# ahrs.net
KiCad netlist of a schematic drawn in EAGLE
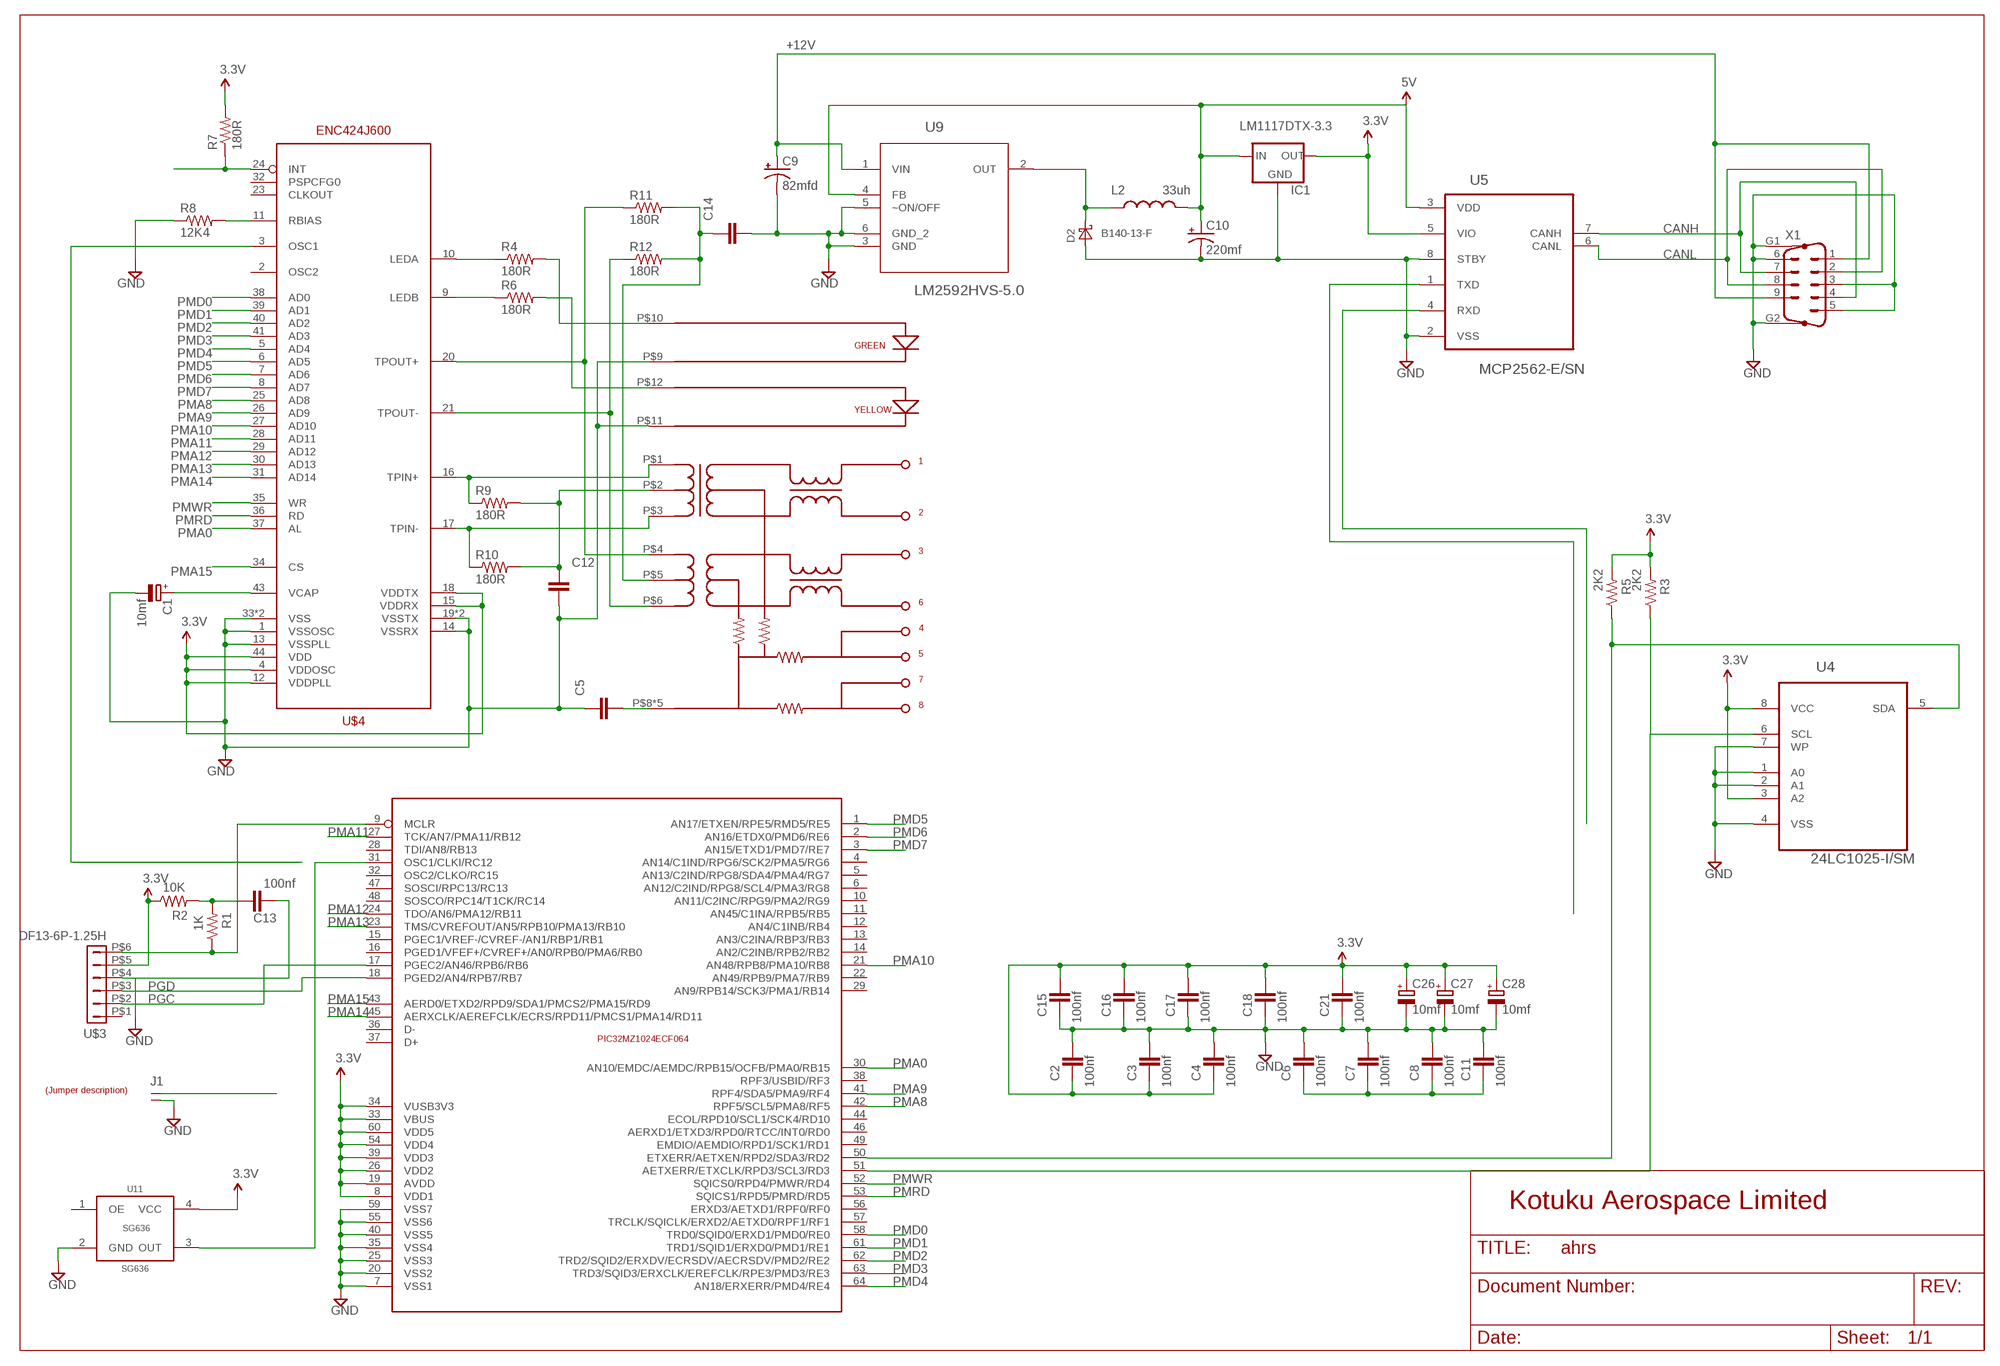
[diagram p0: schematic, sheet 1]

(export (version "E")
  (design (tool "Eeschema 10.0.6"))
  (components
    (comp (ref "C1")
      (value "10mf")
      (footprint "eagle-import:SMC_A")
      (libsource (lib "eagle-import") (part "CAPACITOR_POL-SMC_A"))
    )
    (comp (ref "C2")
      (value "100nf")
      (footprint "eagle-import:C805")
      (libsource (lib "eagle-import") (part "CAPACITOR_NPOL-0805"))
    )
    (comp (ref "C3")
      (value "100nf")
      (footprint "eagle-import:C805")
      (libsource (lib "eagle-import") (part "CAPACITOR_NPOL-0805"))
    )
    (comp (ref "C4")
      (value "100nf")
      (footprint "eagle-import:C805")
      (libsource (lib "eagle-import") (part "CAPACITOR_NPOL-0805"))
    )
    (comp (ref "C5")
      (value "CAPACITOR_NPOL-1206")
      (footprint "eagle-import:C1206")
      (libsource (lib "eagle-import") (part "kotuku_CAPACITOR_NPOL-1206"))
    )
    (comp (ref "C6")
      (value "100nf")
      (footprint "eagle-import:C805")
      (libsource (lib "eagle-import") (part "CAPACITOR_NPOL-0805"))
    )
    (comp (ref "C7")
      (value "100nf")
      (footprint "eagle-import:C805")
      (libsource (lib "eagle-import") (part "CAPACITOR_NPOL-0805"))
    )
    (comp (ref "C8")
      (value "100nf")
      (footprint "eagle-import:C805")
      (libsource (lib "eagle-import") (part "CAPACITOR_NPOL-0805"))
    )
    (comp (ref "C9")
      (value "82mfd")
      (footprint "eagle-import:SVPF-E7")
      (libsource (lib "eagle-import") (part "CAPACITOR_POL-SVPF-E7"))
    )
    (comp (ref "C10")
      (value "220mf")
      (footprint "eagle-import:EIA7343")
      (libsource (lib "eagle-import") (part "CAP_POL7343"))
    )
    (comp (ref "C11")
      (value "100nf")
      (footprint "eagle-import:C805")
      (libsource (lib "eagle-import") (part "CAPACITOR_NPOL-0805"))
    )
    (comp (ref "C12")
      (value "CAPACITOR_NPOL-0603")
      (footprint "eagle-import:C603")
      (libsource (lib "eagle-import") (part "kotuku_CAPACITOR_NPOL-0603"))
    )
    (comp (ref "C13")
      (value "100nf")
      (footprint "eagle-import:C805")
      (libsource (lib "eagle-import") (part "CAPACITOR_NPOL-0805"))
    )
    (comp (ref "C14")
      (value "CAPACITOR_NPOL-0603")
      (footprint "eagle-import:C603")
      (libsource (lib "eagle-import") (part "kotuku_CAPACITOR_NPOL-0603"))
    )
    (comp (ref "C15")
      (value "100nf")
      (footprint "eagle-import:C805")
      (libsource (lib "eagle-import") (part "CAPACITOR_NPOL-0805"))
    )
    (comp (ref "C16")
      (value "100nf")
      (footprint "eagle-import:C805")
      (libsource (lib "eagle-import") (part "CAPACITOR_NPOL-0805"))
    )
    (comp (ref "C17")
      (value "100nf")
      (footprint "eagle-import:C805")
      (libsource (lib "eagle-import") (part "CAPACITOR_NPOL-0805"))
    )
    (comp (ref "C18")
      (value "100nf")
      (footprint "eagle-import:C805")
      (libsource (lib "eagle-import") (part "CAPACITOR_NPOL-0805"))
    )
    (comp (ref "C21")
      (value "100nf")
      (footprint "eagle-import:C805")
      (libsource (lib "eagle-import") (part "CAPACITOR_NPOL-0805"))
    )
    (comp (ref "C26")
      (value "10mf")
      (footprint "eagle-import:SMC_A")
      (libsource (lib "eagle-import") (part "CAPACITOR_POL-SMC_A"))
    )
    (comp (ref "C27")
      (value "10mf")
      (footprint "eagle-import:SMC_A")
      (libsource (lib "eagle-import") (part "CAPACITOR_POL-SMC_A"))
    )
    (comp (ref "C28")
      (value "10mf")
      (footprint "eagle-import:SMC_A")
      (libsource (lib "eagle-import") (part "CAPACITOR_POL-SMC_A"))
    )
    (comp (ref "D2")
      (value "B140-13-F")
      (footprint "eagle-import:SMA")
      (libsource (lib "eagle-import") (part "DIODE-SCHOTTKY-SMA"))
    )
    (comp (ref "IC1")
      (value "LM1117DTX-3.3")
      (footprint "eagle-import:TO252")
      (libsource (lib "eagle-import") (part "LM1117DTX-3.3"))
    )
    (comp (ref "J1")
      (value "JUMPER-1X2")
      (footprint "eagle-import:JUMPER-1X2")
      (libsource (lib "eagle-import") (part "JUMPER-1X2"))
    )
    (comp (ref "L2")
      (value "33uh")
      (footprint "eagle-import:1812")
      (libsource (lib "eagle-import") (part "INDUCTOR"))
    )
    (comp (ref "R1")
      (value "1K")
      (footprint "eagle-import:0603-RES")
      (fields (field (name "PARTNO") "ERJ-3GEYJ103V"))
      (libsource (lib "eagle-import") (part "RESISTOR0603-RES"))
    )
    (comp (ref "R2")
      (value "10K")
      (footprint "eagle-import:0603-RES")
      (fields (field (name "PARTNO") "ERJ-3GEYJ103V"))
      (libsource (lib "eagle-import") (part "RESISTOR0603-RES"))
    )
    (comp (ref "R3")
      (value "2K2")
      (footprint "eagle-import:0603-RES")
      (fields (field (name "PARTNO") "ERJ-3GEYJ103V"))
      (libsource (lib "eagle-import") (part "RESISTOR0603-RES"))
    )
    (comp (ref "R4")
      (value "180R")
      (footprint "eagle-import:0603-RES")
      (libsource (lib "eagle-import") (part "kotuku_RESISTOR0603-RES"))
    )
    (comp (ref "R5")
      (value "2K2")
      (footprint "eagle-import:0603-RES")
      (fields (field (name "PARTNO") "ERJ-3GEYJ103V"))
      (libsource (lib "eagle-import") (part "RESISTOR0603-RES"))
    )
    (comp (ref "R6")
      (value "180R")
      (footprint "eagle-import:0603-RES")
      (libsource (lib "eagle-import") (part "kotuku_RESISTOR0603-RES"))
    )
    (comp (ref "R7")
      (value "180R")
      (footprint "eagle-import:0603-RES")
      (libsource (lib "eagle-import") (part "kotuku_RESISTOR0603-RES"))
    )
    (comp (ref "R8")
      (value "12K4")
      (footprint "eagle-import:0603-RES")
      (libsource (lib "eagle-import") (part "kotuku_RESISTOR0603-RES"))
    )
    (comp (ref "R9")
      (value "180R")
      (footprint "eagle-import:0603-RES")
      (libsource (lib "eagle-import") (part "kotuku_RESISTOR0603-RES"))
    )
    (comp (ref "R10")
      (value "180R")
      (footprint "eagle-import:0603-RES")
      (libsource (lib "eagle-import") (part "kotuku_RESISTOR0603-RES"))
    )
    (comp (ref "R11")
      (value "180R")
      (footprint "eagle-import:0603-RES")
      (libsource (lib "eagle-import") (part "kotuku_RESISTOR0603-RES"))
    )
    (comp (ref "R12")
      (value "180R")
      (footprint "eagle-import:0603-RES")
      (libsource (lib "eagle-import") (part "kotuku_RESISTOR0603-RES"))
    )
    (comp (ref "U$1")
      (value "LABEL_JUMPER_1X2")
      (footprint "eagle-import:JUMP2_DESC")
      (fields (field (name "OFF") "Normal") (field (name "ON") "Reset"))
      (libsource (lib "eagle-import") (part "LABEL_JUMPER_1X2"))
    )
    (comp (ref "U$2")
      (value "PIC32MZ1024")
      (footprint "eagle-import:TQFP-64")
      (libsource (lib "eagle-import") (part "PIC32MZ1024"))
    )
    (comp (ref "U$3")
      (value "DF13-6P-1.25H")
      (footprint "eagle-import:DF13A-6P-1.25H")
      (libsource (lib "eagle-import") (part "DF13-6P-1.25H"))
    )
    (comp (ref "U$4")
      (value "ENC424J600")
      (footprint "eagle-import:TQFP44")
      (libsource (lib "eagle-import") (part "ENC424J600"))
    )
    (comp (ref "U$5")
      (value "J1B1211CCD")
      (footprint "eagle-import:J1B1211CCD")
      (libsource (lib "eagle-import") (part "J1B1211CCD"))
    )
    (comp (ref "U4")
      (value "24LC1025-I/SM")
      (footprint "eagle-import:SOIC8-N_MC")
      (libsource (lib "eagle-import") (part "24LC1025-I/SM"))
    )
    (comp (ref "U5")
      (value "MCP2562-E/SN")
      (footprint "eagle-import:SOIC-8N")
      (libsource (lib "eagle-import") (part "MCP2562-E/SN"))
    )
    (comp (ref "U9")
      (value "LM2592HVS-5.0")
      (footprint "eagle-import:TO170P1435X457-5N")
      (libsource (lib "eagle-import") (part "LM2592HVS-5.0"))
    )
    (comp (ref "U11")
      (value "SG636")
      (footprint "eagle-import:SG636")
      (fields (field (name "PARTNO") "SG-636PCE 10.000MHZ"))
      (libsource (lib "eagle-import") (part "SG636"))
    )
    (comp (ref "X1")
      (value "M09HP")
      (footprint "eagle-import:M09HP")
      (libsource (lib "eagle-import") (part "M09HP"))
    )
  )
  (nets
    (net (code "1") (name "/+12V") (class "Default")
      (node (ref "C9") (pin "P$2") (pinfunction "+_P$2") (pintype "passive"))
      (node (ref "U9") (pin "1") (pinfunction "VIN_1") (pintype "power_in"))
      (node (ref "X1") (pin "1") (pinfunction "1_1") (pintype "passive"))
      (node (ref "X1") (pin "9") (pinfunction "9_9") (pintype "passive"))
    )
    (net (code "2") (name "/CANH") (class "Default")
      (node (ref "U5") (pin "7") (pinfunction "CANH_7") (pintype "bidirectional"))
      (node (ref "X1") (pin "4") (pinfunction "4_4") (pintype "passive"))
      (node (ref "X1") (pin "7") (pinfunction "7_7") (pintype "passive"))
    )
    (net (code "3") (name "/CANL") (class "Default")
      (node (ref "U5") (pin "6") (pinfunction "CANL_6") (pintype "bidirectional"))
      (node (ref "X1") (pin "2") (pinfunction "2_2") (pintype "passive"))
      (node (ref "X1") (pin "8") (pinfunction "8_8") (pintype "passive"))
    )
    (net (code "4") (name "/PGC") (class "Default")
      (node (ref "U$2") (pin "17") (pinfunction "PGEC2/AN46/RPB6/RB6_17") (pintype "bidirectional"))
      (node (ref "U$3") (pin "P$2") (pinfunction "2_P$2") (pintype "passive"))
    )
    (net (code "5") (name "/PGD") (class "Default")
      (node (ref "U$2") (pin "18") (pinfunction "PGED2/AN4/RPB7/RB7_18") (pintype "bidirectional"))
      (node (ref "U$3") (pin "P$3") (pinfunction "3_P$3") (pintype "passive"))
    )
    (net (code "6") (name "/PMA0") (class "Default")
      (node (ref "U$2") (pin "30") (pinfunction "AN10/EMDC/AEMDC/RPB15/OCFB/PMA0/RB15_30") (pintype "bidirectional"))
      (node (ref "U$4") (pin "37") (pinfunction "AL_37") (pintype "bidirectional"))
    )
    (net (code "7") (name "/PMA8") (class "Default")
      (node (ref "U$2") (pin "42") (pinfunction "RPF5/SCL5/PMA8/RF5_42") (pintype "bidirectional"))
      (node (ref "U$4") (pin "25") (pinfunction "AD8_25") (pintype "bidirectional"))
    )
    (net (code "8") (name "/PMA9") (class "Default")
      (node (ref "U$2") (pin "41") (pinfunction "RPF4/SDA5/PMA9/RF4_41") (pintype "bidirectional"))
      (node (ref "U$4") (pin "26") (pinfunction "AD9_26") (pintype "bidirectional"))
    )
    (net (code "9") (name "/PMA10") (class "Default")
      (node (ref "U$2") (pin "21") (pinfunction "AN48/RPB8/PMA10/RB8_21") (pintype "bidirectional"))
      (node (ref "U$4") (pin "27") (pinfunction "AD10_27") (pintype "bidirectional"))
    )
    (net (code "10") (name "/PMA11") (class "Default")
      (node (ref "U$2") (pin "27") (pinfunction "TCK/AN7/PMA11/RB12_27") (pintype "bidirectional"))
      (node (ref "U$4") (pin "28") (pinfunction "AD11_28") (pintype "bidirectional"))
    )
    (net (code "11") (name "/PMA12") (class "Default")
      (node (ref "U$2") (pin "24") (pinfunction "TDO/AN6/PMA12/RB11_24") (pintype "bidirectional"))
      (node (ref "U$4") (pin "29") (pinfunction "AD12_29") (pintype "bidirectional"))
    )
    (net (code "12") (name "/PMA13") (class "Default")
      (node (ref "U$2") (pin "23") (pinfunction "TMS/CVREFOUT/AN5/RPB10/PMA13/RB10_23") (pintype "bidirectional"))
      (node (ref "U$4") (pin "30") (pinfunction "AD13_30") (pintype "bidirectional"))
    )
    (net (code "13") (name "/PMA14") (class "Default")
      (node (ref "U$2") (pin "45") (pinfunction "AERXCLK/AEREFCLK/ECRS/RPD11/PMCS1/PMA14/RD11_45") (pintype "bidirectional"))
      (node (ref "U$4") (pin "31") (pinfunction "AD14_31") (pintype "bidirectional"))
    )
    (net (code "14") (name "/PMA15") (class "Default")
      (node (ref "U$2") (pin "43") (pinfunction "AERD0/ETXD2/RPD9/SDA1/PMCS2/PMA15/RD9_43") (pintype "bidirectional"))
      (node (ref "U$4") (pin "34") (pinfunction "CS_34") (pintype "bidirectional"))
    )
    (net (code "15") (name "/PMD0") (class "Default")
      (node (ref "U$2") (pin "58") (pinfunction "TRD0/SQID0/ERXD1/PMD0/RE0_58") (pintype "bidirectional"))
      (node (ref "U$4") (pin "38") (pinfunction "AD0_38") (pintype "bidirectional"))
    )
    (net (code "16") (name "/PMD1") (class "Default")
      (node (ref "U$2") (pin "61") (pinfunction "TRD1/SQID1/ERXD0/PMD1/RE1_61") (pintype "bidirectional"))
      (node (ref "U$4") (pin "39") (pinfunction "AD1_39") (pintype "bidirectional"))
    )
    (net (code "17") (name "/PMD2") (class "Default")
      (node (ref "U$2") (pin "62") (pinfunction "TRD2/SQID2/ERXDV/ECRSDV/AECRSDV/PMD2/RE2_62") (pintype "bidirectional"))
      (node (ref "U$4") (pin "40") (pinfunction "AD2_40") (pintype "bidirectional"))
    )
    (net (code "18") (name "/PMD3") (class "Default")
      (node (ref "U$2") (pin "63") (pinfunction "TRD3/SQID3/ERXCLK/EREFCLK/RPE3/PMD3/RE3_63") (pintype "bidirectional"))
      (node (ref "U$4") (pin "41") (pinfunction "AD3_41") (pintype "bidirectional"))
    )
    (net (code "19") (name "/PMD4") (class "Default")
      (node (ref "U$2") (pin "64") (pinfunction "AN18/ERXERR/PMD4/RE4_64") (pintype "bidirectional"))
      (node (ref "U$4") (pin "5") (pinfunction "AD4_5") (pintype "bidirectional"))
    )
    (net (code "20") (name "/PMD5") (class "Default")
      (node (ref "U$2") (pin "1") (pinfunction "AN17/ETXEN/RPE5/RMD5/RE5_1") (pintype "bidirectional"))
      (node (ref "U$4") (pin "6") (pinfunction "AD5_6") (pintype "bidirectional"))
    )
    (net (code "21") (name "/PMD6") (class "Default")
      (node (ref "U$2") (pin "2") (pinfunction "AN16/ETDX0/PMD6/RE6_2") (pintype "bidirectional"))
      (node (ref "U$4") (pin "7") (pinfunction "AD6_7") (pintype "bidirectional"))
    )
    (net (code "22") (name "/PMD7") (class "Default")
      (node (ref "U$2") (pin "3") (pinfunction "AN15/ETXD1/PMD7/RE7_3") (pintype "bidirectional"))
      (node (ref "U$4") (pin "8") (pinfunction "AD7_8") (pintype "bidirectional"))
    )
    (net (code "23") (name "/PMRD") (class "Default")
      (node (ref "U$2") (pin "53") (pinfunction "SQICS1/RPD5/PMRD/RD5_53") (pintype "bidirectional"))
      (node (ref "U$4") (pin "36") (pinfunction "RD_36") (pintype "bidirectional"))
    )
    (net (code "24") (name "/PMWR") (class "Default")
      (node (ref "U$2") (pin "52") (pinfunction "SQICS0/RPD4/PMWR/RD4_52") (pintype "bidirectional"))
      (node (ref "U$4") (pin "35") (pinfunction "WR_35") (pintype "bidirectional"))
    )
    (net (code "25") (name "3.3V") (class "Default")
      (node (ref "C15") (pin "1") (pinfunction "1_1") (pintype "passive"))
      (node (ref "C16") (pin "1") (pinfunction "1_1") (pintype "passive"))
      (node (ref "C17") (pin "1") (pinfunction "1_1") (pintype "passive"))
      (node (ref "C18") (pin "1") (pinfunction "1_1") (pintype "passive"))
      (node (ref "C2") (pin "2") (pinfunction "2_2") (pintype "passive"))
      (node (ref "C21") (pin "1") (pinfunction "1_1") (pintype "passive"))
      (node (ref "C26") (pin "+") (pinfunction "+_+") (pintype "passive"))
      (node (ref "C27") (pin "+") (pinfunction "+_+") (pintype "passive"))
      (node (ref "C28") (pin "+") (pinfunction "+_+") (pintype "passive"))
      (node (ref "C3") (pin "2") (pinfunction "2_2") (pintype "passive"))
      (node (ref "C4") (pin "2") (pinfunction "2_2") (pintype "passive"))
      (node (ref "IC1") (pin "TAB") (pinfunction "OUT_TAB") (pintype "passive"))
      (node (ref "R2") (pin "1") (pinfunction "1_1") (pintype "passive"))
      (node (ref "R3") (pin "2") (pinfunction "2_2") (pintype "passive"))
      (node (ref "R5") (pin "2") (pinfunction "2_2") (pintype "passive"))
      (node (ref "R7") (pin "2") (pinfunction "2_2") (pintype "passive"))
      (node (ref "U$2") (pin "19") (pinfunction "AVDD_19") (pintype "bidirectional"))
      (node (ref "U$2") (pin "26") (pinfunction "VDD2_26") (pintype "bidirectional"))
      (node (ref "U$2") (pin "33") (pinfunction "VBUS_33") (pintype "bidirectional"))
      (node (ref "U$2") (pin "34") (pinfunction "VUSB3V3_34") (pintype "bidirectional"))
      (node (ref "U$2") (pin "39") (pinfunction "VDD3_39") (pintype "bidirectional"))
      (node (ref "U$2") (pin "54") (pinfunction "VDD4_54") (pintype "bidirectional"))
      (node (ref "U$2") (pin "60") (pinfunction "VDD5_60") (pintype "bidirectional"))
      (node (ref "U$2") (pin "8") (pinfunction "VDD1_8") (pintype "bidirectional"))
      (node (ref "U$3") (pin "P$5") (pinfunction "5_P$5") (pintype "passive"))
      (node (ref "U$4") (pin "12") (pinfunction "VDDPLL_12") (pintype "bidirectional"))
      (node (ref "U$4") (pin "15") (pinfunction "VDDRX_15") (pintype "bidirectional"))
      (node (ref "U$4") (pin "18") (pinfunction "VDDTX_18") (pintype "bidirectional"))
      (node (ref "U$4") (pin "4") (pinfunction "VDDOSC_4") (pintype "bidirectional"))
      (node (ref "U$4") (pin "44") (pinfunction "VDD_44") (pintype "bidirectional"))
      (node (ref "U11") (pin "4") (pinfunction "VCC_4") (pintype "power_in"))
      (node (ref "U4") (pin "3") (pinfunction "A2_3") (pintype "input"))
      (node (ref "U4") (pin "8") (pinfunction "VCC_8") (pintype "power_in"))
      (node (ref "U5") (pin "5") (pinfunction "VIO_5") (pintype "power_in"))
    )
    (net (code "26") (name "5V") (class "Default")
      (node (ref "C10") (pin "A") (pinfunction "+_A") (pintype "passive"))
      (node (ref "IC1") (pin "2") (pinfunction "IN_2") (pintype "input"))
      (node (ref "L2") (pin "2") (pinfunction "2_2") (pintype "passive"))
      (node (ref "U5") (pin "3") (pinfunction "VDD_3") (pintype "power_in"))
      (node (ref "U9") (pin "4") (pinfunction "FB_4") (pintype "input"))
    )
    (net (code "27") (name "GND") (class "Default")
      (node (ref "C1") (pin "-") (pinfunction "-_-") (pintype "passive"))
      (node (ref "C10") (pin "C") (pinfunction "-_C") (pintype "passive"))
      (node (ref "C11") (pin "1") (pinfunction "1_1") (pintype "passive"))
      (node (ref "C12") (pin "2") (pinfunction "2_2") (pintype "passive"))
      (node (ref "C13") (pin "2") (pinfunction "2_2") (pintype "passive"))
      (node (ref "C14") (pin "2") (pinfunction "2_2") (pintype "passive"))
      (node (ref "C15") (pin "2") (pinfunction "2_2") (pintype "passive"))
      (node (ref "C16") (pin "2") (pinfunction "2_2") (pintype "passive"))
      (node (ref "C17") (pin "2") (pinfunction "2_2") (pintype "passive"))
      (node (ref "C18") (pin "2") (pinfunction "2_2") (pintype "passive"))
      (node (ref "C2") (pin "1") (pinfunction "1_1") (pintype "passive"))
      (node (ref "C21") (pin "2") (pinfunction "2_2") (pintype "passive"))
      (node (ref "C26") (pin "-") (pinfunction "-_-") (pintype "passive"))
      (node (ref "C27") (pin "-") (pinfunction "-_-") (pintype "passive"))
      (node (ref "C28") (pin "-") (pinfunction "-_-") (pintype "passive"))
      (node (ref "C3") (pin "1") (pinfunction "1_1") (pintype "passive"))
      (node (ref "C4") (pin "1") (pinfunction "1_1") (pintype "passive"))
      (node (ref "C5") (pin "1") (pinfunction "1_1") (pintype "passive"))
      (node (ref "C6") (pin "1") (pinfunction "1_1") (pintype "passive"))
      (node (ref "C7") (pin "1") (pinfunction "1_1") (pintype "passive"))
      (node (ref "C8") (pin "1") (pinfunction "1_1") (pintype "passive"))
      (node (ref "C9") (pin "P$1") (pinfunction "-_P$1") (pintype "passive"))
      (node (ref "D2") (pin "A") (pinfunction "A_A") (pintype "passive"))
      (node (ref "IC1") (pin "1") (pinfunction "GND_1") (pintype "input"))
      (node (ref "J1") (pin "2") (pinfunction "2_2") (pintype "bidirectional"))
      (node (ref "R8") (pin "1") (pinfunction "1_1") (pintype "passive"))
      (node (ref "U$2") (pin "20") (pinfunction "VSS2_20") (pintype "bidirectional"))
      (node (ref "U$2") (pin "25") (pinfunction "VSS3_25") (pintype "bidirectional"))
      (node (ref "U$2") (pin "35") (pinfunction "VSS4_35") (pintype "bidirectional"))
      (node (ref "U$2") (pin "40") (pinfunction "VSS5_40") (pintype "bidirectional"))
      (node (ref "U$2") (pin "55") (pinfunction "VSS6_55") (pintype "bidirectional"))
      (node (ref "U$2") (pin "59") (pinfunction "VSS7_59") (pintype "bidirectional"))
      (node (ref "U$2") (pin "7") (pinfunction "VSS1_7") (pintype "bidirectional"))
      (node (ref "U$3") (pin "P$4") (pinfunction "4_P$4") (pintype "passive"))
      (node (ref "U$4") (pin "1") (pinfunction "VSSOSC_1") (pintype "bidirectional"))
      (node (ref "U$4") (pin "13") (pinfunction "VSSPLL_13") (pintype "bidirectional"))
      (node (ref "U$4") (pin "14") (pinfunction "VSSRX_14") (pintype "bidirectional"))
      (node (ref "U$4") (pin "19") (pinfunction "VSSTX_19") (pintype "bidirectional"))
      (node (ref "U$4") (pin "22") (pinfunction "VSSTX_22") (pintype "bidirectional"))
      (node (ref "U$4") (pin "33") (pinfunction "VSS_33") (pintype "bidirectional"))
      (node (ref "U$4") (pin "42") (pinfunction "VSS_42") (pintype "bidirectional"))
      (node (ref "U$5") (pin "P$11") (pinfunction "YELLOW_K_P$11") (pintype "bidirectional"))
      (node (ref "U$5") (pin "P$9") (pinfunction "GREEN_K_P$9") (pintype "bidirectional"))
      (node (ref "U11") (pin "2") (pinfunction "GND_2") (pintype "power_in"))
      (node (ref "U4") (pin "1") (pinfunction "A0_1") (pintype "input"))
      (node (ref "U4") (pin "2") (pinfunction "A1_2") (pintype "input"))
      (node (ref "U4") (pin "4") (pinfunction "VSS_4") (pintype "passive"))
      (node (ref "U4") (pin "7") (pinfunction "WP_7") (pintype "input"))
      (node (ref "U5") (pin "2") (pinfunction "VSS_2") (pintype "power_in"))
      (node (ref "U5") (pin "8") (pinfunction "STBY_8") (pintype "input"))
      (node (ref "U9") (pin "3") (pinfunction "GND_3") (pintype "passive"))
      (node (ref "U9") (pin "5") (pinfunction "~{ON/OFF}_5") (pintype "input"))
      (node (ref "U9") (pin "6") (pinfunction "GND_2_6") (pintype "passive"))
      (node (ref "X1") (pin "3") (pinfunction "3_3") (pintype "passive"))
      (node (ref "X1") (pin "5") (pinfunction "5_5") (pintype "passive"))
      (node (ref "X1") (pin "6") (pinfunction "6_6") (pintype "passive"))
      (node (ref "X1") (pin "G1") (pinfunction "G1_G1") (pintype "passive"))
      (node (ref "X1") (pin "G2") (pinfunction "G2_G2") (pintype "passive"))
    )
    (net (code "28") (name "Net-(C5-Pad2)") (class "Default")
      (node (ref "C5") (pin "2") (pinfunction "2_2") (pintype "passive"))
      (node (ref "U$5") (pin "P$13") (pinfunction "GNDIN_P$13") (pintype "bidirectional"))
      (node (ref "U$5") (pin "P$14") (pinfunction "GNDIN_P$14") (pintype "bidirectional"))
      (node (ref "U$5") (pin "P$15") (pinfunction "GNDIN_P$15") (pintype "bidirectional"))
      (node (ref "U$5") (pin "P$16") (pinfunction "GNDIN_P$16") (pintype "bidirectional"))
      (node (ref "U$5") (pin "P$8") (pinfunction "GNDIN_P$8") (pintype "bidirectional"))
    )
    (net (code "29") (name "Net-(C11-Pad2)") (class "Default")
      (node (ref "C11") (pin "2") (pinfunction "2_2") (pintype "passive"))
      (node (ref "C6") (pin "2") (pinfunction "2_2") (pintype "passive"))
      (node (ref "C7") (pin "2") (pinfunction "2_2") (pintype "passive"))
      (node (ref "C8") (pin "2") (pinfunction "2_2") (pintype "passive"))
    )
    (net (code "30") (name "Net-(C13-Pad1)") (class "Default")
      (node (ref "C13") (pin "1") (pinfunction "1_1") (pintype "passive"))
      (node (ref "R1") (pin "2") (pinfunction "2_2") (pintype "passive"))
      (node (ref "R2") (pin "2") (pinfunction "2_2") (pintype "passive"))
    )
    (net (code "31") (name "Net-(U$2-AETXERR{slash}ETXCLK{slash}RPD3{slash}SCL3{slash}RD3)") (class "Default")
      (node (ref "R3") (pin "1") (pinfunction "1_1") (pintype "passive"))
      (node (ref "U$2") (pin "51") (pinfunction "AETXERR/ETXCLK/RPD3/SCL3/RD3_51") (pintype "bidirectional"))
      (node (ref "U4") (pin "6") (pinfunction "SCL_6") (pintype "input"))
    )
    (net (code "32") (name "Net-(U$2-ETXERR{slash}AETXEN{slash}RPD2{slash}SDA3{slash}RD2)") (class "Default")
      (node (ref "R5") (pin "1") (pinfunction "1_1") (pintype "passive"))
      (node (ref "U$2") (pin "50") (pinfunction "ETXERR/AETXEN/RPD2/SDA3/RD2_50") (pintype "bidirectional"))
      (node (ref "U4") (pin "5") (pinfunction "SDA_5") (pintype "bidirectional"))
    )
    (net (code "33") (name "Net-(U$2-MCLR)") (class "Default")
      (node (ref "R1") (pin "1") (pinfunction "1_1") (pintype "passive"))
      (node (ref "U$2") (pin "9") (pinfunction "MCLR_9") (pintype "input"))
      (node (ref "U$3") (pin "P$6") (pinfunction "6_P$6") (pintype "passive"))
    )
    (net (code "34") (name "Net-(U$2-OSC1{slash}CLKI{slash}RC12)") (class "Default")
      (node (ref "U$2") (pin "31") (pinfunction "OSC1/CLKI/RC12_31") (pintype "bidirectional"))
      (node (ref "U11") (pin "3") (pinfunction "OUT_3") (pintype "output"))
    )
    (net (code "35") (name "Net-(U$4-INT)") (class "Default")
      (node (ref "R7") (pin "1") (pinfunction "1_1") (pintype "passive"))
      (node (ref "U$4") (pin "24") (pinfunction "INT_24") (pintype "bidirectional"))
    )
    (net (code "36") (name "Net-(U$4-LEDA)") (class "Default")
      (node (ref "R4") (pin "1") (pinfunction "1_1") (pintype "passive"))
      (node (ref "U$4") (pin "10") (pinfunction "LEDA_10") (pintype "bidirectional"))
    )
    (net (code "37") (name "Net-(U$4-LEDB)") (class "Default")
      (node (ref "R6") (pin "1") (pinfunction "1_1") (pintype "passive"))
      (node (ref "U$4") (pin "9") (pinfunction "LEDB_9") (pintype "bidirectional"))
    )
    (net (code "38") (name "Net-(U$4-RBIAS)") (class "Default")
      (node (ref "R8") (pin "2") (pinfunction "2_2") (pintype "passive"))
      (node (ref "U$4") (pin "11") (pinfunction "RBIAS_11") (pintype "bidirectional"))
    )
    (net (code "39") (name "Net-(U$4-TPIN+)") (class "Default")
      (node (ref "R9") (pin "1") (pinfunction "1_1") (pintype "passive"))
      (node (ref "U$4") (pin "16") (pinfunction "TPIN+_16") (pintype "bidirectional"))
      (node (ref "U$5") (pin "P$1") (pinfunction "TX+_P$1") (pintype "bidirectional"))
    )
    (net (code "40") (name "Net-(U$4-TPIN-)") (class "Default")
      (node (ref "R10") (pin "1") (pinfunction "1_1") (pintype "passive"))
      (node (ref "U$4") (pin "17") (pinfunction "TPIN-_17") (pintype "bidirectional"))
      (node (ref "U$5") (pin "P$3") (pinfunction "TX-_P$3") (pintype "bidirectional"))
    )
    (net (code "41") (name "Net-(U$4-TPOUT+)") (class "Default")
      (node (ref "R11") (pin "1") (pinfunction "1_1") (pintype "passive"))
      (node (ref "U$4") (pin "20") (pinfunction "TPOUT+_20") (pintype "bidirectional"))
      (node (ref "U$5") (pin "P$4") (pinfunction "RX+_P$4") (pintype "bidirectional"))
    )
    (net (code "42") (name "Net-(U$4-TPOUT-)") (class "Default")
      (node (ref "R12") (pin "1") (pinfunction "1_1") (pintype "passive"))
      (node (ref "U$4") (pin "21") (pinfunction "TPOUT-_21") (pintype "bidirectional"))
      (node (ref "U$5") (pin "P$6") (pinfunction "RX-_P$6") (pintype "bidirectional"))
    )
    (net (code "43") (name "Net-(U$4-VCAP)") (class "Default")
      (node (ref "C1") (pin "+") (pinfunction "+_+") (pintype "passive"))
      (node (ref "U$4") (pin "43") (pinfunction "VCAP_43") (pintype "bidirectional"))
    )
    (net (code "44") (name "Net-(U$5-GREEN_A)") (class "Default")
      (node (ref "R4") (pin "2") (pinfunction "2_2") (pintype "passive"))
      (node (ref "U$5") (pin "P$10") (pinfunction "GREEN_A_P$10") (pintype "bidirectional"))
    )
    (net (code "45") (name "Net-(U$5-P2IN)") (class "Default")
      (node (ref "C12") (pin "1") (pinfunction "1_1") (pintype "passive"))
      (node (ref "R10") (pin "2") (pinfunction "2_2") (pintype "passive"))
      (node (ref "R9") (pin "2") (pinfunction "2_2") (pintype "passive"))
      (node (ref "U$5") (pin "P$2") (pinfunction "P2IN_P$2") (pintype "bidirectional"))
    )
    (net (code "46") (name "Net-(U$5-P5IN)") (class "Default")
      (node (ref "C14") (pin "1") (pinfunction "1_1") (pintype "passive"))
      (node (ref "R11") (pin "2") (pinfunction "2_2") (pintype "passive"))
      (node (ref "U$5") (pin "P$5") (pinfunction "P5IN_P$5") (pintype "bidirectional"))
    )
    (net (code "47") (name "Net-(U$5-YELLOW_A)") (class "Default")
      (node (ref "R6") (pin "2") (pinfunction "2_2") (pintype "passive"))
      (node (ref "U$5") (pin "P$12") (pinfunction "YELLOW_A_P$12") (pintype "bidirectional"))
    )
    (net (code "48") (name "Net-(U9-OUT)") (class "Default")
      (node (ref "D2") (pin "C") (pinfunction "C_C") (pintype "passive"))
      (node (ref "L2") (pin "1") (pinfunction "1_1") (pintype "passive"))
      (node (ref "U9") (pin "2") (pinfunction "OUT_2") (pintype "output"))
    )
    (net (code "49") (name "unconnected-(J1-Pad1)") (class "Default")
      (node (ref "J1") (pin "1") (pinfunction "1_1") (pintype "bidirectional"))
    )
    (net (code "50") (name "unconnected-(R12-Pad2)") (class "Default")
      (node (ref "R12") (pin "2") (pinfunction "2_2") (pintype "passive"))
    )
    (net (code "51") (name "unconnected-(U$2-AERXD1{slash}ETXD3{slash}RPD0{slash}RTCC{slash}INT0{slash}RD0-Pad46)") (class "Default")
      (node (ref "U$2") (pin "46") (pinfunction "AERXD1/ETXD3/RPD0/RTCC/INT0/RD0_46") (pintype "bidirectional"))
    )
    (net (code "52") (name "unconnected-(U$2-AN2{slash}C2INB{slash}RPB2{slash}RB2-Pad14)") (class "Default")
      (node (ref "U$2") (pin "14") (pinfunction "AN2/C2INB/RPB2/RB2_14") (pintype "bidirectional"))
    )
    (net (code "53") (name "unconnected-(U$2-AN3{slash}C2INA{slash}RBP3{slash}RB3-Pad13)") (class "Default")
      (node (ref "U$2") (pin "13") (pinfunction "AN3/C2INA/RBP3/RB3_13") (pintype "bidirectional"))
    )
    (net (code "54") (name "unconnected-(U$2-AN4{slash}C1INB{slash}RB4-Pad12)") (class "Default")
      (node (ref "U$2") (pin "12") (pinfunction "AN4/C1INB/RB4_12") (pintype "bidirectional"))
    )
    (net (code "55") (name "unconnected-(U$2-AN9{slash}RPB14{slash}SCK3{slash}PMA1{slash}RB14-Pad29)") (class "Default")
      (node (ref "U$2") (pin "29") (pinfunction "AN9/RPB14/SCK3/PMA1/RB14_29") (pintype "bidirectional"))
    )
    (net (code "56") (name "unconnected-(U$2-AN11{slash}C2INC{slash}RPG9{slash}PMA2{slash}RG9-Pad10)") (class "Default")
      (node (ref "U$2") (pin "10") (pinfunction "AN11/C2INC/RPG9/PMA2/RG9_10") (pintype "bidirectional"))
    )
    (net (code "57") (name "unconnected-(U$2-AN12{slash}C2IND{slash}RPG8{slash}SCL4{slash}PMA3{slash}RG8-Pad6)") (class "Default")
      (node (ref "U$2") (pin "6") (pinfunction "AN12/C2IND/RPG8/SCL4/PMA3/RG8_6") (pintype "bidirectional"))
    )
    (net (code "58") (name "unconnected-(U$2-AN13{slash}C2IND{slash}RPG8{slash}SDA4{slash}PMA4{slash}RG7-Pad5)") (class "Default")
      (node (ref "U$2") (pin "5") (pinfunction "AN13/C2IND/RPG8/SDA4/PMA4/RG7_5") (pintype "bidirectional"))
    )
    (net (code "59") (name "unconnected-(U$2-AN14{slash}C1IND{slash}RPG6{slash}SCK2{slash}PMA5{slash}RG6-Pad4)") (class "Default")
      (node (ref "U$2") (pin "4") (pinfunction "AN14/C1IND/RPG6/SCK2/PMA5/RG6_4") (pintype "bidirectional"))
    )
    (net (code "60") (name "unconnected-(U$2-AN45{slash}C1INA{slash}RPB5{slash}RB5-Pad11)") (class "Default")
      (node (ref "U$2") (pin "11") (pinfunction "AN45/C1INA/RPB5/RB5_11") (pintype "bidirectional"))
    )
    (net (code "61") (name "unconnected-(U$2-AN49{slash}RPB9{slash}PMA7{slash}RB9-Pad22)") (class "Default")
      (node (ref "U$2") (pin "22") (pinfunction "AN49/RPB9/PMA7/RB9_22") (pintype "bidirectional"))
    )
    (net (code "62") (name "unconnected-(U$2-D+-Pad37)") (class "Default")
      (node (ref "U$2") (pin "37") (pinfunction "D+_37") (pintype "bidirectional"))
    )
    (net (code "63") (name "unconnected-(U$2-D--Pad36)") (class "Default")
      (node (ref "U$2") (pin "36") (pinfunction "D-_36") (pintype "bidirectional"))
    )
    (net (code "64") (name "unconnected-(U$2-ECOL{slash}RPD10{slash}SCL1{slash}SCK4{slash}RD10-Pad44)") (class "Default")
      (node (ref "U$2") (pin "44") (pinfunction "ECOL/RPD10/SCL1/SCK4/RD10_44") (pintype "bidirectional"))
    )
    (net (code "65") (name "unconnected-(U$2-EMDIO{slash}AEMDIO{slash}RPD1{slash}SCK1{slash}RD1-Pad49)") (class "Default")
      (node (ref "U$2") (pin "49") (pinfunction "EMDIO/AEMDIO/RPD1/SCK1/RD1_49") (pintype "bidirectional"))
    )
    (net (code "66") (name "unconnected-(U$2-ERXD3{slash}AETXD1{slash}RPF0{slash}RF0-Pad56)") (class "Default")
      (node (ref "U$2") (pin "56") (pinfunction "ERXD3/AETXD1/RPF0/RF0_56") (pintype "bidirectional"))
    )
    (net (code "67") (name "unconnected-(U$2-OSC2{slash}CLKO{slash}RC15-Pad32)") (class "Default")
      (node (ref "U$2") (pin "32") (pinfunction "OSC2/CLKO/RC15_32") (pintype "bidirectional"))
    )
    (net (code "68") (name "unconnected-(U$2-PGEC1{slash}VREF-{slash}CVREF-{slash}AN1{slash}RBP1{slash}RB1-Pad15)") (class "Default")
      (node (ref "U$2") (pin "15") (pinfunction "PGEC1/VREF-/CVREF-/AN1/RBP1/RB1_15") (pintype "bidirectional"))
    )
    (net (code "69") (name "unconnected-(U$2-PGED1{slash}VFEF+{slash}CVREF+{slash}AN0{slash}RPB0{slash}PMA6{slash}RB0-Pad16)") (class "Default")
      (node (ref "U$2") (pin "16") (pinfunction "PGED1/VFEF+/CVREF+/AN0/RPB0/PMA6/RB0_16") (pintype "bidirectional"))
    )
    (net (code "70") (name "unconnected-(U$2-RPF3{slash}USBID{slash}RF3-Pad38)") (class "Default")
      (node (ref "U$2") (pin "38") (pinfunction "RPF3/USBID/RF3_38") (pintype "bidirectional"))
    )
    (net (code "71") (name "unconnected-(U$2-SOSCI{slash}RPC13{slash}RC13-Pad47)") (class "Default")
      (node (ref "U$2") (pin "47") (pinfunction "SOSCI/RPC13/RC13_47") (pintype "bidirectional"))
    )
    (net (code "72") (name "unconnected-(U$2-SOSCO{slash}RPC14{slash}T1CK{slash}RC14-Pad48)") (class "Default")
      (node (ref "U$2") (pin "48") (pinfunction "SOSCO/RPC14/T1CK/RC14_48") (pintype "bidirectional"))
    )
    (net (code "73") (name "unconnected-(U$2-TDI{slash}AN8{slash}RB13-Pad28)") (class "Default")
      (node (ref "U$2") (pin "28") (pinfunction "TDI/AN8/RB13_28") (pintype "bidirectional"))
    )
    (net (code "74") (name "unconnected-(U$2-TRCLK{slash}SQICLK{slash}ERXD2{slash}AETXD0{slash}RPF1{slash}RF1-Pad57)") (class "Default")
      (node (ref "U$2") (pin "57") (pinfunction "TRCLK/SQICLK/ERXD2/AETXD0/RPF1/RF1_57") (pintype "bidirectional"))
    )
    (net (code "75") (name "unconnected-(U$3-1-PadP$1)") (class "Default")
      (node (ref "U$3") (pin "P$1") (pinfunction "1_P$1") (pintype "passive"))
    )
    (net (code "76") (name "unconnected-(U$4-CLKOUT-Pad23)") (class "Default")
      (node (ref "U$4") (pin "23") (pinfunction "CLKOUT_23") (pintype "bidirectional"))
    )
    (net (code "77") (name "unconnected-(U$4-OSC1-Pad3)") (class "Default")
      (node (ref "U$4") (pin "3") (pinfunction "OSC1_3") (pintype "bidirectional"))
    )
    (net (code "78") (name "unconnected-(U$4-OSC2-Pad2)") (class "Default")
      (node (ref "U$4") (pin "2") (pinfunction "OSC2_2") (pintype "bidirectional"))
    )
    (net (code "79") (name "unconnected-(U$4-PSPCFG0-Pad32)") (class "Default")
      (node (ref "U$4") (pin "32") (pinfunction "PSPCFG0_32") (pintype "bidirectional"))
    )
    (net (code "80") (name "unconnected-(U5-RXD-Pad4)") (class "Default")
      (node (ref "U5") (pin "4") (pinfunction "RXD_4") (pintype "output"))
    )
    (net (code "81") (name "unconnected-(U5-TXD-Pad1)") (class "Default")
      (node (ref "U5") (pin "1") (pinfunction "TXD_1") (pintype "input"))
    )
    (net (code "82") (name "unconnected-(U11-OE-Pad1)") (class "Default")
      (node (ref "U11") (pin "1") (pinfunction "OE_1") (pintype "input"))
    )
  )
)
